# Microcontroller.net
KiCad netlist of a schematic drawn in Altium Designer
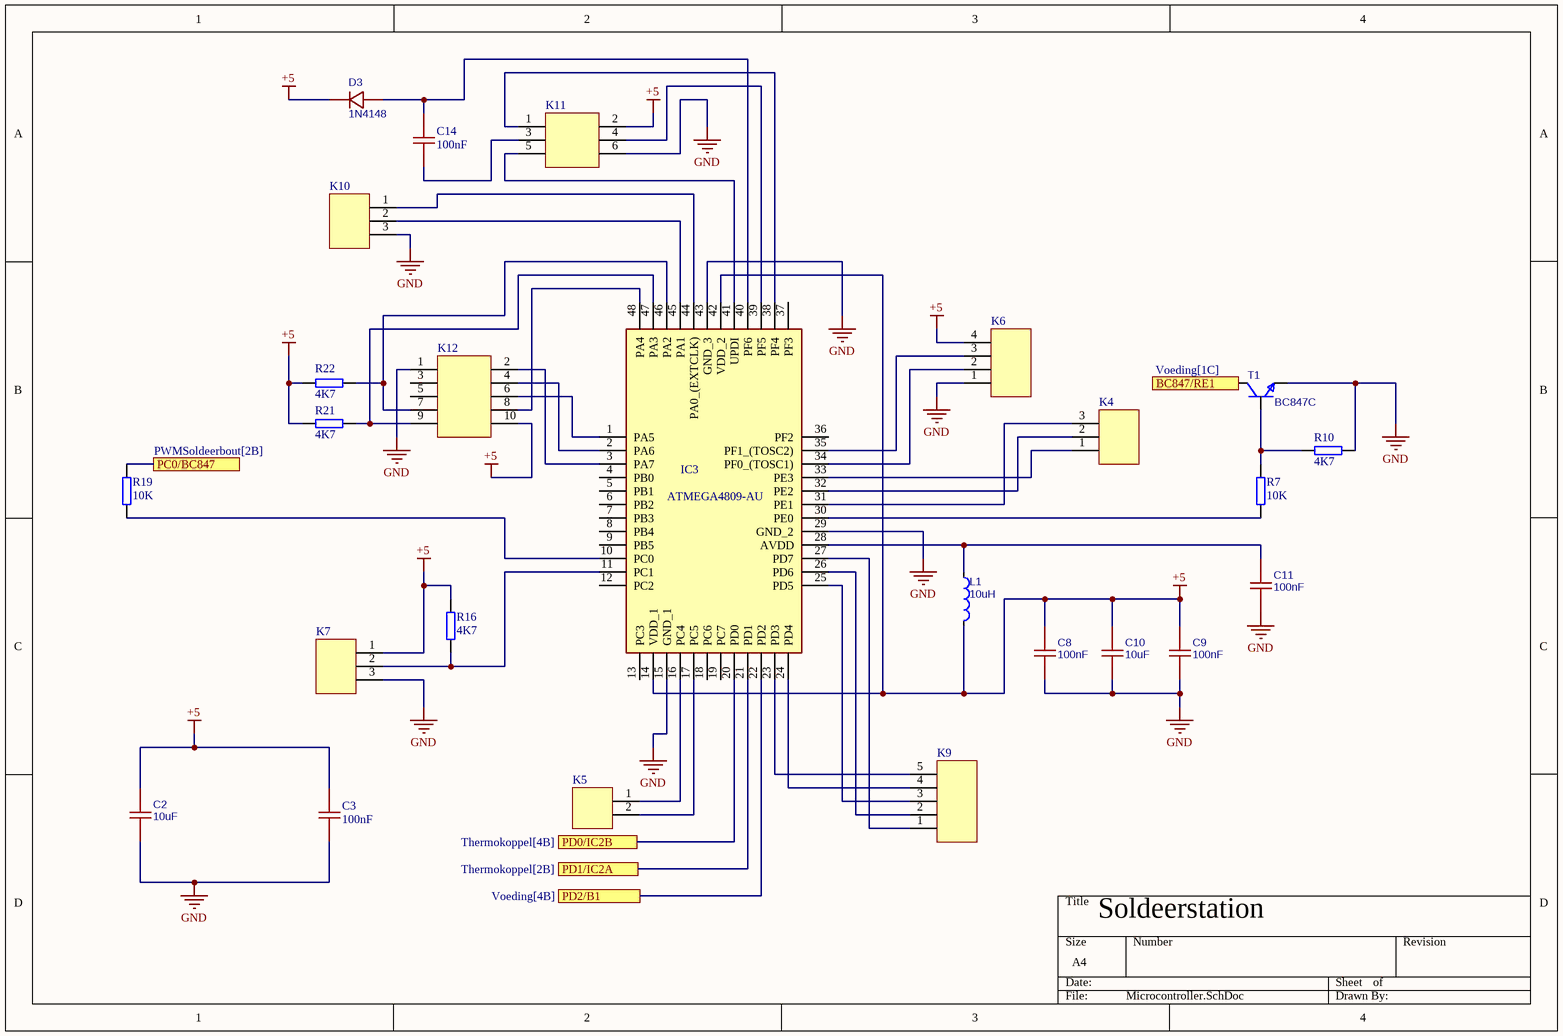
[diagram p0: Microcontroller.SchDoc]

(export (version "E")
  (design (tool "Eeschema 10.0.6"))
  (components
    (comp (ref "C2")
      (value "10uF")
      (footprint "C2,5,10 10uF")
      (fields
        (field (name "BOM_SUPPLIER PART") "C440198")
        (field (name "BOM_MANUFACTURER PART") "GRM21BR61H106KE43L")
        (field (name "CONTRIBUTOR") "LCSC")
      )
      (libsource (lib "SoldeerStation") (part "C2,5,10 10uF"))
    )
    (comp (ref "C3")
      (value "100nF")
      (footprint "C6,7,12,13 10nF")
      (libsource (lib "SoldeerStation") (part "C 100nF"))
    )
    (comp (ref "C8")
      (value "100nF")
      (footprint "C6,7,12,13 10nF")
      (fields
        (field (name "BOM_SUPPLIER PART") "C376921")
        (field (name "BOM_MANUFACTURER PART") "TCC0805X7R103M500DT")
        (field (name "CONTRIBUTOR") "LCSC")
      )
      (libsource (lib "SoldeerStation") (part "C6,7,12,13 10nF"))
    )
    (comp (ref "C9")
      (value "100nF")
      (footprint "C6,7,12,13 10nF")
      (fields
        (field (name "BOM_SUPPLIER PART") "C376921")
        (field (name "BOM_MANUFACTURER PART") "TCC0805X7R103M500DT")
        (field (name "CONTRIBUTOR") "LCSC")
      )
      (libsource (lib "SoldeerStation") (part "C6,7,12,13 10nF"))
    )
    (comp (ref "C10")
      (value "10uF")
      (footprint "C2,5,10 10uF")
      (fields
        (field (name "BOM_SUPPLIER PART") "C440198")
        (field (name "BOM_MANUFACTURER PART") "GRM21BR61H106KE43L")
        (field (name "CONTRIBUTOR") "LCSC")
      )
      (libsource (lib "SoldeerStation") (part "C2,5,10 10uF"))
    )
    (comp (ref "C11")
      (value "100nF")
      (footprint "C6,7,12,13 10nF")
      (fields
        (field (name "BOM_SUPPLIER PART") "C376921")
        (field (name "BOM_MANUFACTURER PART") "TCC0805X7R103M500DT")
        (field (name "CONTRIBUTOR") "LCSC")
      )
      (libsource (lib "SoldeerStation") (part "C6,7,12,13 10nF"))
    )
    (comp (ref "C14")
      (value "100nF")
      (footprint "C6,7,12,13 10nF")
      (libsource (lib "SoldeerStation") (part "C 100nF"))
    )
    (comp (ref "D3")
      (value "1N4148")
      (footprint "D3 1N14148")
      (description "1N4148W-C84367")
      (fields (field (name "BOM_MANUFACTURER PART") "1N4148W") (field (name "BOM_SUPPLIER PART") "C84367"))
      (libsource (lib "SoldeerStation") (part "D3 1N14148"))
    )
    (comp (ref "IC3")
      (value "ATMEGA4809-AU")
      (footprint "IC3 ATMEGA4809-AU")
      (description "8-bit Microcontrollers - MCU 20MHz, 48KB, TQFP")
      (fields (field (name "MOUSER PART NUMBER") "556-ATMEGA4809-AU"))
      (libsource (lib "SoldeerStation") (part "IC3 ATMEGA4809-AU"))
    )
    (comp (ref "K4")
      (value "~")
      (footprint "PInHeader_3")
      (libsource (lib "SoldeerStation") (part "K PinHeader_3"))
    )
    (comp (ref "K5")
      (value "~")
      (footprint "PInHeader_2")
      (libsource (lib "SoldeerStation") (part "K PinHeader_2"))
    )
    (comp (ref "K6")
      (value "~")
      (footprint "PInHeader_4")
      (libsource (lib "SoldeerStation") (part "K PinHeader_4"))
    )
    (comp (ref "K7") (value "~") (footprint "PInHeader_3") (libsource (lib "") (part "K PinHeader_3_1")))
    (comp (ref "K9")
      (value "~")
      (footprint "PInHeader_5")
      (libsource (lib "SoldeerStation") (part "K PinHeader_5"))
    )
    (comp (ref "K10") (value "~") (footprint "PInHeader_3") (libsource (lib "") (part "K PinHeader_3_1")))
    (comp (ref "K11")
      (value "~")
      (footprint "PInHeader_6")
      (libsource (lib "SoldeerStation") (part "K PinHeader_6"))
    )
    (comp (ref "K12")
      (value "~")
      (footprint "BOxHeader_10")
      (libsource (lib "SoldeerStation") (part "K Boxheader_10"))
    )
    (comp (ref "L1")
      (value "10uH")
      (footprint "L2 SmoorSpoel")
      (fields
        (field (name "BOM_SUPPLIER PART") "C2922559")
        (field (name "BOM_MANUFACTURER PART") "PMI201214S-100M")
        (field (name "CONTRIBUTOR") "LCSC")
      )
      (libsource (lib "SoldeerStation") (part "L2 smoorspoel"))
    )
    (comp (ref "R7")
      (value "10K")
      (footprint "RESC2013X50X30ML20T20")
      (fields (field (name "MANUFACTURER") "Vishay Dale") (field (name "PART NUMBER") "CRCW08050000Z0EA"))
      (libsource (lib "SoldeerStation") (part "R Resistor"))
    )
    (comp (ref "R10")
      (value "4K7")
      (footprint "RESC2013X50X30ML20T20")
      (fields (field (name "MANUFACTURER") "Vishay Dale") (field (name "PART NUMBER") "CRCW08050000Z0EA"))
      (libsource (lib "SoldeerStation") (part "R Resistor"))
    )
    (comp (ref "R16")
      (value "4K7")
      (footprint "RESC2013X50X30ML20T20")
      (fields (field (name "MANUFACTURER") "Vishay Dale") (field (name "PART NUMBER") "CRCW08050000Z0EA"))
      (libsource (lib "SoldeerStation") (part "R Resistor"))
    )
    (comp (ref "R19")
      (value "10K")
      (footprint "RESC2013X50X30ML20T20")
      (fields (field (name "MANUFACTURER") "Vishay Dale") (field (name "PART NUMBER") "CRCW08050000Z0EA"))
      (libsource (lib "SoldeerStation") (part "R Resistor"))
    )
    (comp (ref "R21")
      (value "4K7")
      (footprint "RESC2013X50X30ML20T20")
      (fields (field (name "MANUFACTURER") "Vishay Dale") (field (name "PART NUMBER") "CRCW08050000Z0EA"))
      (libsource (lib "SoldeerStation") (part "R Resistor"))
    )
    (comp (ref "R22")
      (value "4K7")
      (footprint "RESC2013X50X30ML20T20")
      (fields (field (name "MANUFACTURER") "Vishay Dale") (field (name "PART NUMBER") "CRCW08050000Z0EA"))
      (libsource (lib "SoldeerStation") (part "R Resistor"))
    )
    (comp (ref "T1")
      (value "BC847C")
      (footprint "T1,2,4 Bipolar Transistors")
      (description "BC847C_C3027113")
      (fields (field (name "BOM_SUPPLIER PART") "C3027113") (field (name "CONTRIBUTOR") "lcsc"))
      (libsource (lib "SoldeerStation") (part "T1,2,4 transisitors"))
    )
  )
  (nets
    (net (code "1") (name "+5") (class "Default")
      (node (ref "C10") (pin "2") (pinfunction "2_2") (pintype "passive"))
      (node (ref "C2") (pin "2") (pinfunction "2_2") (pintype "passive"))
      (node (ref "C3") (pin "2") (pinfunction "2_2") (pintype "passive"))
      (node (ref "C8") (pin "1") (pinfunction "1_1") (pintype "passive"))
      (node (ref "C9") (pin "1") (pinfunction "1_1") (pintype "passive"))
      (node (ref "D3") (pin "1") (pinfunction "C_1") (pintype "passive"))
      (node (ref "IC3") (pin "14") (pinfunction "VDD_1_14") (pintype "passive"))
      (node (ref "IC3") (pin "42") (pinfunction "VDD_2_42") (pintype "passive"))
      (node (ref "K11") (pin "2") (pintype "passive"))
      (node (ref "K12") (pin "10") (pintype "passive"))
      (node (ref "K6") (pin "4") (pintype "passive"))
      (node (ref "K7") (pin "1") (pintype "passive"))
      (node (ref "L1") (pin "2") (pinfunction "2_2") (pintype "passive"))
      (node (ref "R16") (pin "2") (pinfunction "2_2") (pintype "passive"))
      (node (ref "R21") (pin "1") (pinfunction "1_1") (pintype "passive"))
      (node (ref "R22") (pin "1") (pinfunction "1_1") (pintype "passive"))
    )
    (net (code "3") (name "/PC0{slash}BC847") (class "Default")
      (node (ref "R19") (pin "2") (pinfunction "2_2") (pintype "passive"))
    )
    (net (code "4") (name "/PD0{slash}IC2B") (class "Default")
      (node (ref "IC3") (pin "20") (pinfunction "PD0_20") (pintype "passive"))
    )
    (net (code "5") (name "/PD1{slash}IC2A") (class "Default")
      (node (ref "IC3") (pin "21") (pinfunction "PD1_21") (pintype "passive"))
    )
    (net (code "6") (name "/PD2{slash}B1") (class "Default")
      (node (ref "IC3") (pin "22") (pinfunction "PD2_22") (pintype "passive"))
    )
    (net (code "7") (name "GND") (class "Default")
      (node (ref "C10") (pin "1") (pinfunction "1_1") (pintype "passive"))
      (node (ref "C11") (pin "2") (pinfunction "2_2") (pintype "passive"))
      (node (ref "C2") (pin "1") (pinfunction "1_1") (pintype "passive"))
      (node (ref "C3") (pin "1") (pinfunction "1_1") (pintype "passive"))
      (node (ref "C8") (pin "2") (pinfunction "2_2") (pintype "passive"))
      (node (ref "C9") (pin "2") (pinfunction "2_2") (pintype "passive"))
      (node (ref "IC3") (pin "15") (pinfunction "GND_1_15") (pintype "passive"))
      (node (ref "IC3") (pin "29") (pinfunction "GND_2_29") (pintype "passive"))
      (node (ref "IC3") (pin "43") (pinfunction "GND_3_43") (pintype "passive"))
      (node (ref "K10") (pin "3") (pintype "passive"))
      (node (ref "K11") (pin "6") (pintype "passive"))
      (node (ref "K12") (pin "1") (pintype "passive"))
      (node (ref "K6") (pin "1") (pintype "passive"))
      (node (ref "K7") (pin "3") (pintype "passive"))
      (node (ref "R10") (pin "2") (pinfunction "2_2") (pintype "passive"))
      (node (ref "T1") (pin "2") (pinfunction "E_2") (pintype "passive"))
    )
    (net (code "8") (name "Net-(C14-Pad1)") (class "Default")
      (node (ref "C14") (pin "1") (pinfunction "1_1") (pintype "passive"))
      (node (ref "K11") (pin "3") (pintype "passive"))
    )
    (net (code "9") (name "Net-(D3-A)") (class "Default")
      (node (ref "C14") (pin "2") (pinfunction "2_2") (pintype "passive"))
      (node (ref "D3") (pin "2") (pinfunction "A_2") (pintype "passive"))
      (node (ref "IC3") (pin "40") (pinfunction "PF6_40") (pintype "passive"))
    )
    (net (code "10") (name "Net-(IC3-AVDD)") (class "Default")
      (node (ref "C11") (pin "1") (pinfunction "1_1") (pintype "passive"))
      (node (ref "IC3") (pin "28") (pinfunction "AVDD_28") (pintype "passive"))
      (node (ref "L1") (pin "1") (pinfunction "1_1") (pintype "passive"))
    )
    (net (code "11") (name "Net-(IC3-PA0_(EXTCLK))") (class "Default")
      (node (ref "IC3") (pin "44") (pinfunction "PA0_(EXTCLK)_44") (pintype "passive"))
      (node (ref "K10") (pin "1") (pintype "passive"))
    )
    (net (code "12") (name "Net-(IC3-PA1)") (class "Default")
      (node (ref "IC3") (pin "45") (pinfunction "PA1_45") (pintype "passive"))
      (node (ref "K10") (pin "2") (pintype "passive"))
    )
    (net (code "13") (name "Net-(IC3-PA2)") (class "Default")
      (node (ref "IC3") (pin "46") (pinfunction "PA2_46") (pintype "passive"))
      (node (ref "K12") (pin "7") (pintype "passive"))
      (node (ref "R22") (pin "2") (pinfunction "2_2") (pintype "passive"))
    )
    (net (code "14") (name "Net-(IC3-PA3)") (class "Default")
      (node (ref "IC3") (pin "47") (pinfunction "PA3_47") (pintype "passive"))
      (node (ref "K12") (pin "9") (pintype "passive"))
      (node (ref "R21") (pin "2") (pinfunction "2_2") (pintype "passive"))
    )
    (net (code "15") (name "Net-(IC3-PA4)") (class "Default")
      (node (ref "IC3") (pin "48") (pinfunction "PA4_48") (pintype "passive"))
      (node (ref "K12") (pin "8") (pintype "passive"))
    )
    (net (code "16") (name "Net-(IC3-PA5)") (class "Default")
      (node (ref "IC3") (pin "1") (pinfunction "PA5_1") (pintype "passive"))
      (node (ref "K12") (pin "6") (pintype "passive"))
    )
    (net (code "17") (name "Net-(IC3-PA6)") (class "Default")
      (node (ref "IC3") (pin "2") (pinfunction "PA6_2") (pintype "passive"))
      (node (ref "K12") (pin "4") (pintype "passive"))
    )
    (net (code "18") (name "Net-(IC3-PA7)") (class "Default")
      (node (ref "IC3") (pin "3") (pinfunction "PA7_3") (pintype "passive"))
      (node (ref "K12") (pin "2") (pintype "passive"))
    )
    (net (code "19") (name "Net-(IC3-PC0)") (class "Default")
      (node (ref "IC3") (pin "10") (pinfunction "PC0_10") (pintype "passive"))
      (node (ref "R19") (pin "1") (pinfunction "1_1") (pintype "passive"))
    )
    (net (code "20") (name "Net-(IC3-PC1)") (class "Default")
      (node (ref "IC3") (pin "11") (pinfunction "PC1_11") (pintype "passive"))
      (node (ref "K7") (pin "2") (pintype "passive"))
      (node (ref "R16") (pin "1") (pinfunction "1_1") (pintype "passive"))
    )
    (net (code "21") (name "Net-(IC3-PC4)") (class "Default")
      (node (ref "IC3") (pin "16") (pinfunction "PC4_16") (pintype "passive"))
      (node (ref "K5") (pin "1") (pintype "passive"))
    )
    (net (code "22") (name "Net-(IC3-PC5)") (class "Default")
      (node (ref "IC3") (pin "17") (pinfunction "PC5_17") (pintype "passive"))
      (node (ref "K5") (pin "2") (pintype "passive"))
    )
    (net (code "23") (name "Net-(IC3-PD3)") (class "Default")
      (node (ref "IC3") (pin "23") (pinfunction "PD3_23") (pintype "passive"))
      (node (ref "K9") (pin "5") (pintype "passive"))
    )
    (net (code "24") (name "Net-(IC3-PD4)") (class "Default")
      (node (ref "IC3") (pin "24") (pinfunction "PD4_24") (pintype "passive"))
      (node (ref "K9") (pin "4") (pintype "passive"))
    )
    (net (code "25") (name "Net-(IC3-PD5)") (class "Default")
      (node (ref "IC3") (pin "25") (pinfunction "PD5_25") (pintype "passive"))
      (node (ref "K9") (pin "3") (pintype "passive"))
    )
    (net (code "26") (name "Net-(IC3-PD6)") (class "Default")
      (node (ref "IC3") (pin "26") (pinfunction "PD6_26") (pintype "passive"))
      (node (ref "K9") (pin "2") (pintype "passive"))
    )
    (net (code "27") (name "Net-(IC3-PD7)") (class "Default")
      (node (ref "IC3") (pin "27") (pinfunction "PD7_27") (pintype "passive"))
      (node (ref "K9") (pin "1") (pintype "passive"))
    )
    (net (code "28") (name "Net-(IC3-PE0)") (class "Default")
      (node (ref "IC3") (pin "30") (pinfunction "PE0_30") (pintype "passive"))
      (node (ref "R7") (pin "1") (pinfunction "1_1") (pintype "passive"))
    )
    (net (code "29") (name "Net-(IC3-PE1)") (class "Default")
      (node (ref "IC3") (pin "31") (pinfunction "PE1_31") (pintype "passive"))
      (node (ref "K4") (pin "3") (pintype "passive"))
    )
    (net (code "30") (name "Net-(IC3-PE2)") (class "Default")
      (node (ref "IC3") (pin "32") (pinfunction "PE2_32") (pintype "passive"))
      (node (ref "K4") (pin "2") (pintype "passive"))
    )
    (net (code "31") (name "Net-(IC3-PE3)") (class "Default")
      (node (ref "IC3") (pin "33") (pinfunction "PE3_33") (pintype "passive"))
      (node (ref "K4") (pin "1") (pintype "passive"))
    )
    (net (code "32") (name "Net-(IC3-PF0_(TOSC1))") (class "Default")
      (node (ref "IC3") (pin "34") (pinfunction "PF0_(TOSC1)_34") (pintype "passive"))
      (node (ref "K6") (pin "2") (pintype "passive"))
    )
    (net (code "33") (name "Net-(IC3-PF1_(TOSC2))") (class "Default")
      (node (ref "IC3") (pin "35") (pinfunction "PF1_(TOSC2)_35") (pintype "passive"))
      (node (ref "K6") (pin "3") (pintype "passive"))
    )
    (net (code "34") (name "Net-(IC3-PF4)") (class "Default")
      (node (ref "IC3") (pin "38") (pinfunction "PF4_38") (pintype "passive"))
      (node (ref "K11") (pin "1") (pintype "passive"))
    )
    (net (code "35") (name "Net-(IC3-PF5)") (class "Default")
      (node (ref "IC3") (pin "39") (pinfunction "PF5_39") (pintype "passive"))
      (node (ref "K11") (pin "4") (pintype "passive"))
    )
    (net (code "36") (name "Net-(IC3-UPDI)") (class "Default")
      (node (ref "IC3") (pin "41") (pinfunction "UPDI_41") (pintype "passive"))
      (node (ref "K11") (pin "5") (pintype "passive"))
    )
    (net (code "37") (name "Net-(T1-B)") (class "Default")
      (node (ref "R10") (pin "1") (pinfunction "1_1") (pintype "passive"))
      (node (ref "R7") (pin "2") (pinfunction "2_2") (pintype "passive"))
      (node (ref "T1") (pin "1") (pinfunction "B_1") (pintype "passive"))
    )
    (net (code "38") (name "unconnected-(IC3-PB0-Pad4)") (class "Default")
      (node (ref "IC3") (pin "4") (pinfunction "PB0_4") (pintype "passive"))
    )
    (net (code "39") (name "unconnected-(IC3-PB1-Pad5)") (class "Default")
      (node (ref "IC3") (pin "5") (pinfunction "PB1_5") (pintype "passive"))
    )
    (net (code "40") (name "unconnected-(IC3-PB2-Pad6)") (class "Default")
      (node (ref "IC3") (pin "6") (pinfunction "PB2_6") (pintype "passive"))
    )
    (net (code "41") (name "unconnected-(IC3-PB3-Pad7)") (class "Default")
      (node (ref "IC3") (pin "7") (pinfunction "PB3_7") (pintype "passive"))
    )
    (net (code "42") (name "unconnected-(IC3-PB4-Pad8)") (class "Default")
      (node (ref "IC3") (pin "8") (pinfunction "PB4_8") (pintype "passive"))
    )
    (net (code "43") (name "unconnected-(IC3-PB5-Pad9)") (class "Default")
      (node (ref "IC3") (pin "9") (pinfunction "PB5_9") (pintype "passive"))
    )
    (net (code "44") (name "unconnected-(IC3-PC2-Pad12)") (class "Default")
      (node (ref "IC3") (pin "12") (pinfunction "PC2_12") (pintype "passive"))
    )
    (net (code "45") (name "unconnected-(IC3-PC3-Pad13)") (class "Default")
      (node (ref "IC3") (pin "13") (pinfunction "PC3_13") (pintype "passive"))
    )
    (net (code "46") (name "unconnected-(IC3-PC6-Pad18)") (class "Default")
      (node (ref "IC3") (pin "18") (pinfunction "PC6_18") (pintype "passive"))
    )
    (net (code "47") (name "unconnected-(IC3-PC7-Pad19)") (class "Default")
      (node (ref "IC3") (pin "19") (pinfunction "PC7_19") (pintype "passive"))
    )
    (net (code "48") (name "unconnected-(IC3-PF2-Pad36)") (class "Default")
      (node (ref "IC3") (pin "36") (pinfunction "PF2_36") (pintype "passive"))
    )
    (net (code "49") (name "unconnected-(IC3-PF3-Pad37)") (class "Default")
      (node (ref "IC3") (pin "37") (pinfunction "PF3_37") (pintype "passive"))
    )
    (net (code "50") (name "unconnected-(K12-Pad3)") (class "Default")
      (node (ref "K12") (pin "3") (pintype "passive"))
    )
    (net (code "51") (name "unconnected-(K12-Pad5)") (class "Default")
      (node (ref "K12") (pin "5") (pintype "passive"))
    )
    (net (code "52") (name "unconnected-(T1-C-Pad3)") (class "Default")
      (node (ref "T1") (pin "3") (pinfunction "C_3") (pintype "passive"))
    )
  )
)
